# WL_144.net
KiCad netlist of a schematic drawn in Altium Designer
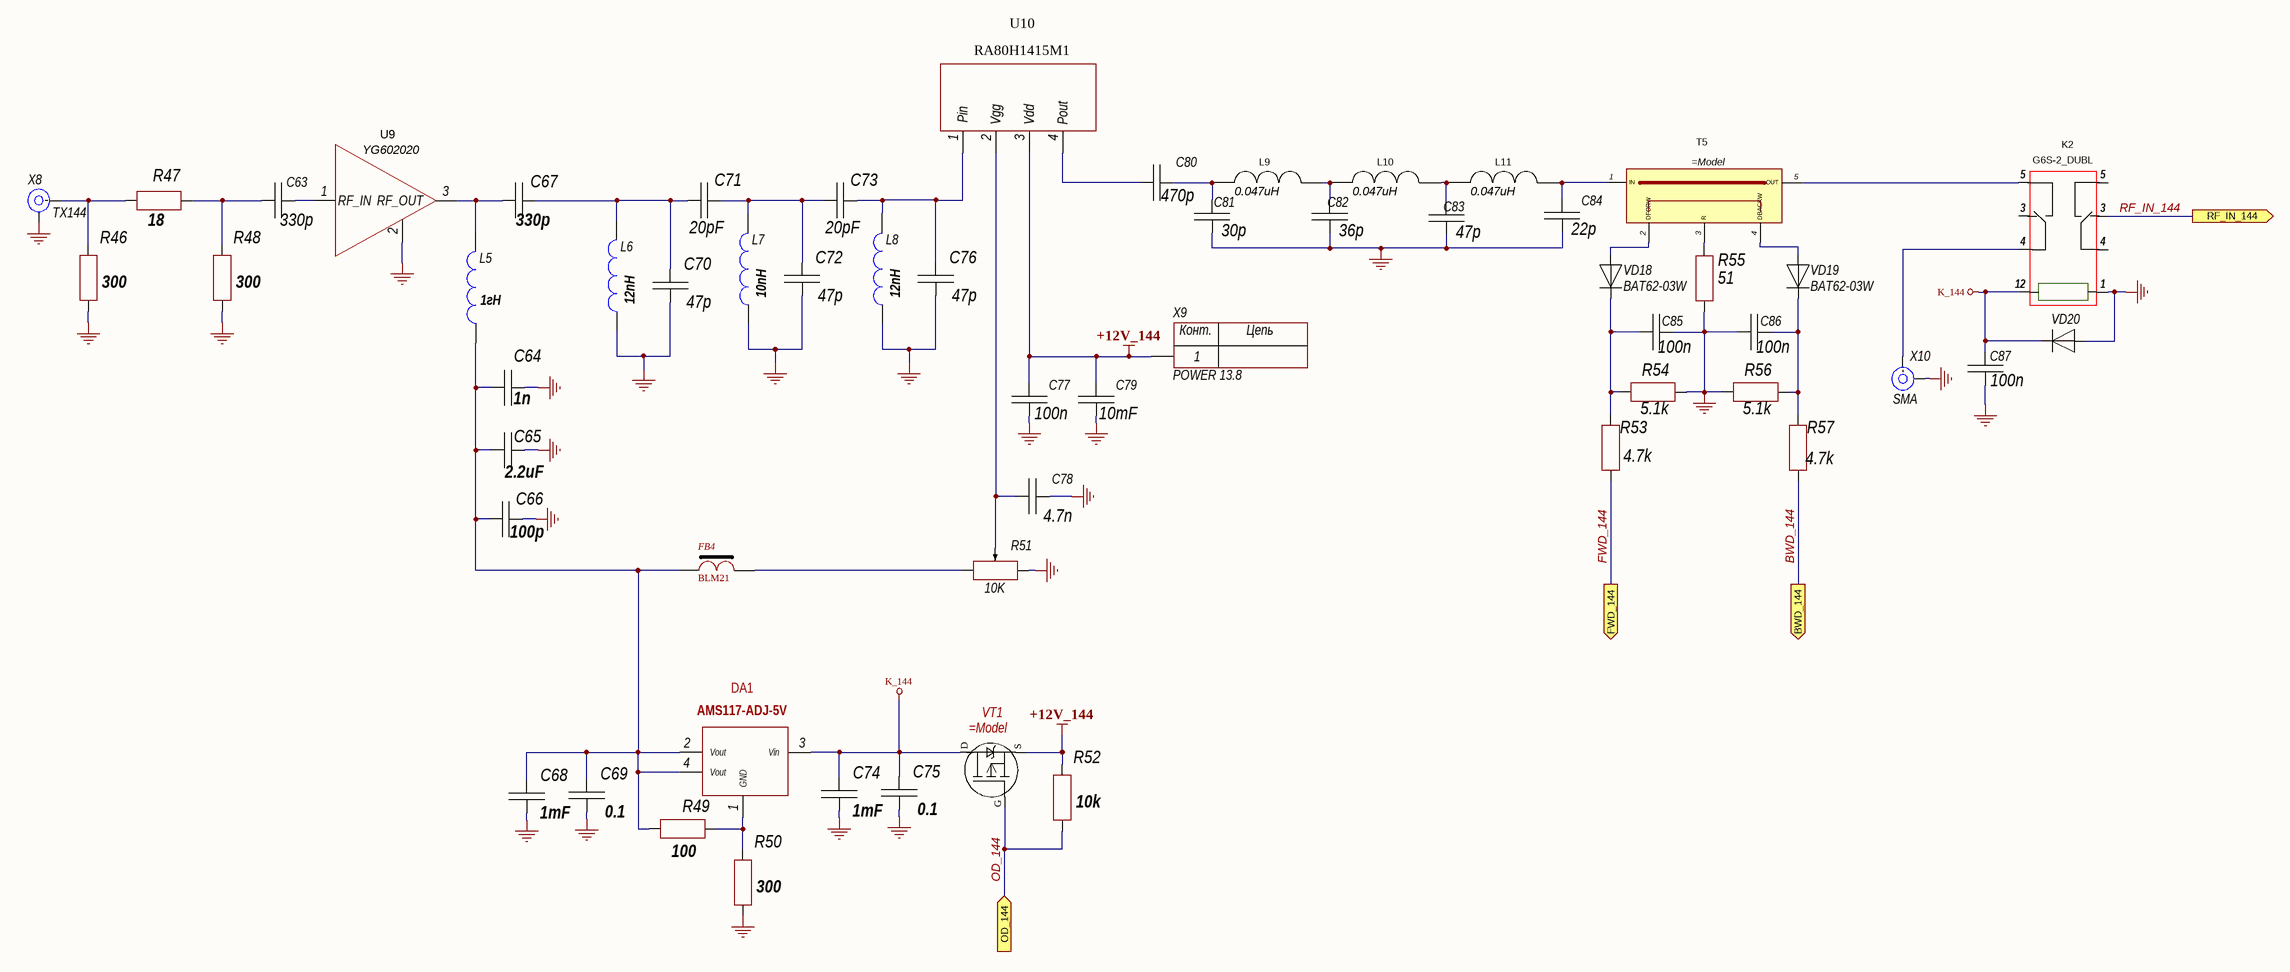
[diagram p0: WL_144.SchDoc]

(export (version "E")
  (design (tool "Eeschema 10.0.6"))
  (components
    (comp (ref "C63")
      (value "330p")
      (footprint "standard:CH0805C")
      (libsource (lib "Discrete") (part "Capacitor"))
    )
    (comp (ref "C64")
      (value "1n")
      (footprint "standard:CH0805C")
      (libsource (lib "Discrete") (part "Capacitor"))
    )
    (comp (ref "C65")
      (value "2.2uF")
      (footprint "standard:CH0805C")
      (libsource (lib "") (part "Capacitor_1"))
    )
    (comp (ref "C66")
      (value "100p")
      (footprint "standard:CH0805C")
      (libsource (lib "Discrete") (part "Capacitor"))
    )
    (comp (ref "C67")
      (value "330p")
      (footprint "standard:CH0805C")
      (libsource (lib "Discrete") (part "Capacitor"))
    )
    (comp (ref "C68")
      (value "1mF")
      (footprint "standard:CH0805C")
      (libsource (lib "Discrete") (part "Capacitor"))
    )
    (comp (ref "C69")
      (value "0.1")
      (footprint "standard:CH0805C")
      (libsource (lib "Discrete") (part "Capacitor"))
    )
    (comp (ref "C70")
      (value "47p")
      (footprint "standard:CH0805C")
      (libsource (lib "Discrete") (part "Capacitor"))
    )
    (comp (ref "C71")
      (value "20pF")
      (footprint "standard:CH0805C")
      (libsource (lib "Discrete") (part "Capacitor"))
    )
    (comp (ref "C72")
      (value "47p")
      (footprint "standard:CH0805C")
      (libsource (lib "Discrete") (part "Capacitor"))
    )
    (comp (ref "C73")
      (value "20pF")
      (footprint "standard:CH0805C")
      (libsource (lib "Discrete") (part "Capacitor"))
    )
    (comp (ref "C74")
      (value "1mF")
      (footprint "standard:CH0805C")
      (libsource (lib "Discrete") (part "Capacitor"))
    )
    (comp (ref "C75")
      (value "0.1")
      (footprint "standard:CH0805C")
      (libsource (lib "Discrete") (part "Capacitor"))
    )
    (comp (ref "C76")
      (value "47p")
      (footprint "standard:CH0805C")
      (libsource (lib "Discrete") (part "Capacitor"))
    )
    (comp (ref "C77")
      (value "100n")
      (footprint "standard:CH1206C")
      (libsource (lib "Discrete") (part "Capacitor"))
    )
    (comp (ref "C78")
      (value "4.7n")
      (footprint "standard:CH0805C")
      (libsource (lib "Discrete") (part "Capacitor"))
    )
    (comp (ref "C79")
      (value "10mF")
      (footprint "standard:CH1206C")
      (libsource (lib "Discrete") (part "Capacitor"))
    )
    (comp (ref "C80")
      (value "470p")
      (footprint "standard:CH1206C")
      (libsource (lib "Discrete") (part "Capacitor"))
    )
    (comp (ref "C81")
      (value "30p")
      (footprint "standard:CH1206C")
      (libsource (lib "Discrete") (part "Capacitor"))
    )
    (comp (ref "C82")
      (value "36p")
      (footprint "standard:CH1206C")
      (libsource (lib "Discrete") (part "Capacitor"))
    )
    (comp (ref "C83")
      (value "47p")
      (footprint "standard:CH1206C")
      (libsource (lib "Discrete") (part "Capacitor"))
    )
    (comp (ref "C84")
      (value "22p")
      (footprint "standard:CH1206C")
      (libsource (lib "Discrete") (part "Capacitor"))
    )
    (comp (ref "C85")
      (value "100n")
      (footprint "standard:CH0805C")
      (libsource (lib "Discrete") (part "Capacitor"))
    )
    (comp (ref "C86")
      (value "100n")
      (footprint "standard:CH0805C")
      (libsource (lib "Discrete") (part "Capacitor"))
    )
    (comp (ref "C87")
      (value "100n")
      (footprint "standard:CH0805C")
      (libsource (lib "Discrete") (part "Capacitor"))
    )
    (comp (ref "DA1") (value "AMS117-ADJ-5V") (footprint "SOT223") (libsource (lib "Analog") (part "AMS117")))
    (comp (ref "FB4") (value "BLM21") (footprint "CH0805L") (libsource (lib "Discrete") (part "FB-1")))
    (comp (ref "K2")
      (value "G6S-2_DUBL")
      (footprint "G6S-2_DUBL")
      (libsource (lib "Relay") (part "G6S-2_DUBL"))
    )
    (comp (ref "L5")
      (value "1гH")
      (footprint "katuhka")
      (libsource (lib "Transformers") (part "Inductor ring"))
    )
    (comp (ref "L6")
      (value "12nH")
      (footprint "katuhka")
      (libsource (lib "Transformers") (part "Inductor ring"))
    )
    (comp (ref "L7")
      (value "10nH")
      (footprint "katuhka")
      (libsource (lib "Transformers") (part "Inductor ring"))
    )
    (comp (ref "L8")
      (value "12nH")
      (footprint "katuhka")
      (libsource (lib "Transformers") (part "Inductor ring"))
    )
    (comp (ref "L9")
      (value "0.047uH")
      (footprint "L-FNC_V3")
      (libsource (lib "Transformers") (part "TRANS-1"))
    )
    (comp (ref "L10")
      (value "0.047uH")
      (footprint "L-FNC_V3")
      (libsource (lib "Transformers") (part "TRANS-1"))
    )
    (comp (ref "L11")
      (value "0.047uH")
      (footprint "L-FNC_V3")
      (libsource (lib "Transformers") (part "TRANS-1"))
    )
    (comp (ref "R46") (value "300") (footprint "standard:CH0805R") (libsource (lib "") (part "Resistor_1")))
    (comp (ref "R47")
      (value "18")
      (footprint "standard:CH0805R")
      (libsource (lib "Discrete") (part "Resistor"))
    )
    (comp (ref "R48") (value "300") (footprint "standard:CH0805R") (libsource (lib "") (part "Resistor_1")))
    (comp (ref "R49")
      (value "100")
      (footprint "standard:CH0805R")
      (libsource (lib "Discrete") (part "Resistor"))
    )
    (comp (ref "R50") (value "300") (footprint "standard:CH0805R") (libsource (lib "") (part "Resistor_1")))
    (comp (ref "R51")
      (value "10K")
      (footprint "custom:RES: 3296W")
      (libsource (lib "Discrete") (part "ADJ resistor"))
    )
    (comp (ref "R52") (value "10k") (footprint "standard:CH0805R") (libsource (lib "") (part "Resistor_1")))
    (comp (ref "R53") (value "4.7k") (footprint "standard:CH0805R") (libsource (lib "") (part "Resistor_2")))
    (comp (ref "R54")
      (value "5.1k")
      (footprint "standard:CH0805R")
      (libsource (lib "Discrete") (part "Resistor"))
    )
    (comp (ref "R55") (value "51") (footprint "standard:CH1206R") (libsource (lib "") (part "Resistor_1")))
    (comp (ref "R56")
      (value "5.1k")
      (footprint "standard:CH0805R")
      (libsource (lib "Discrete") (part "Resistor"))
    )
    (comp (ref "R57") (value "4.7k") (footprint "standard:CH0805R") (libsource (lib "") (part "Resistor_2")))
    (comp (ref "T5") (value "~") (footprint "SWR_D") (libsource (lib "Transformers") (part "VHF_KSV1")))
    (comp (ref "U9") (value "YG602020") (footprint "SOT89_123") (libsource (lib "Digital") (part "YG602020")))
    (comp (ref "U10")
      (value "RA80H1415M1")
      (footprint "RA80H1415M1 - duplicate")
      (libsource (lib "Digital") (part "RA80H1415M1"))
    )
    (comp (ref "VD18") (value "BAT62-03W") (footprint "1N4148") (libsource (lib "Diods") (part "Diod")))
    (comp (ref "VD19") (value "BAT62-03W") (footprint "1N4148") (libsource (lib "Diods") (part "Diod")))
    (comp (ref "VD20") (value "~") (footprint "1N4148") (libsource (lib "Diods") (part "Diod")))
    (comp (ref "VT1") (value "~") (footprint "SOT23_132") (libsource (lib "Transistor") (part "P-KANAL")))
    (comp (ref "X8")
      (value "TX144")
      (footprint "CON: u.Fl")
      (description "RF")
      (libsource (lib "Connectors") (part "SMA"))
    )
    (comp (ref "X9")
      (value "POWER 13.8")
      (footprint "CON: KNIFE_5MM")
      (libsource (lib "Connectors") (part "1-Connector"))
    )
    (comp (ref "X10")
      (value "SMA")
      (footprint "custom:CON: SMA")
      (description "RF")
      (libsource (lib "Connectors") (part "SMA"))
    )
  )
  (nets
    (net (code "1") (name "+12V_144") (class "Default")
      (node (ref "C77") (pin "2") (pinfunction "2_2") (pintype "power_in"))
      (node (ref "C79") (pin "2") (pinfunction "2_2") (pintype "power_in"))
      (node (ref "R52") (pin "2") (pinfunction "2_2") (pintype "passive"))
      (node (ref "U10") (pin "3") (pinfunction "Vdd_3") (pintype "passive"))
      (node (ref "VT1") (pin "2") (pinfunction "Исток_2") (pintype "passive"))
      (node (ref "X9") (pin "1") (pinfunction "1_1") (pintype "passive"))
    )
    (net (code "2") (name "/BWD_144") (class "Default")
      (node (ref "R57") (pin "2") (pinfunction "2_2") (pintype "passive"))
    )
    (net (code "3") (name "/FWD_144") (class "Default")
      (node (ref "R53") (pin "2") (pinfunction "2_2") (pintype "passive"))
    )
    (net (code "4") (name "/OD_144") (class "Default")
      (node (ref "R52") (pin "1") (pinfunction "1_1") (pintype "passive"))
      (node (ref "VT1") (pin "1") (pinfunction "Затвор(Gate)_1") (pintype "passive"))
    )
    (net (code "5") (name "/RF_IN_144") (class "Default")
      (node (ref "K2") (pin "3") (pinfunction "3_3") (pintype "passive"))
    )
    (net (code "6") (name "GND") (class "Default")
      (node (ref "C64") (pin "2") (pinfunction "2_2") (pintype "power_in"))
      (node (ref "C65") (pin "2") (pinfunction "2_2") (pintype "power_in"))
      (node (ref "C66") (pin "2") (pinfunction "2_2") (pintype "power_in"))
      (node (ref "C68") (pin "1") (pinfunction "1_1") (pintype "power_in"))
      (node (ref "C69") (pin "1") (pinfunction "1_1") (pintype "power_in"))
      (node (ref "C70") (pin "1") (pinfunction "1_1") (pintype "power_in"))
      (node (ref "C72") (pin "1") (pinfunction "1_1") (pintype "power_in"))
      (node (ref "C74") (pin "1") (pinfunction "1_1") (pintype "power_in"))
      (node (ref "C75") (pin "1") (pinfunction "1_1") (pintype "power_in"))
      (node (ref "C76") (pin "1") (pinfunction "1_1") (pintype "power_in"))
      (node (ref "C77") (pin "1") (pinfunction "1_1") (pintype "power_in"))
      (node (ref "C78") (pin "1") (pinfunction "1_1") (pintype "power_in"))
      (node (ref "C79") (pin "1") (pinfunction "1_1") (pintype "power_in"))
      (node (ref "C81") (pin "1") (pinfunction "1_1") (pintype "power_in"))
      (node (ref "C82") (pin "1") (pinfunction "1_1") (pintype "power_in"))
      (node (ref "C83") (pin "1") (pinfunction "1_1") (pintype "power_in"))
      (node (ref "C84") (pin "1") (pinfunction "1_1") (pintype "power_in"))
      (node (ref "C85") (pin "1") (pinfunction "1_1") (pintype "power_in"))
      (node (ref "C86") (pin "2") (pinfunction "2_2") (pintype "power_in"))
      (node (ref "C87") (pin "2") (pinfunction "2_2") (pintype "power_in"))
      (node (ref "K2") (pin "1") (pinfunction "1_1") (pintype "passive"))
      (node (ref "L6") (pin "2") (pinfunction "2_2") (pintype "passive"))
      (node (ref "L7") (pin "2") (pinfunction "2_2") (pintype "passive"))
      (node (ref "L8") (pin "2") (pinfunction "2_2") (pintype "passive"))
      (node (ref "R46") (pin "1") (pinfunction "1_1") (pintype "passive"))
      (node (ref "R48") (pin "1") (pinfunction "1_1") (pintype "passive"))
      (node (ref "R50") (pin "1") (pinfunction "1_1") (pintype "passive"))
      (node (ref "R51") (pin "1") (pinfunction "1_1") (pintype "passive"))
      (node (ref "R54") (pin "1") (pinfunction "1_1") (pintype "passive"))
      (node (ref "R55") (pin "1") (pinfunction "1_1") (pintype "passive"))
      (node (ref "R56") (pin "2") (pinfunction "2_2") (pintype "passive"))
      (node (ref "U9") (pin "2") (pinfunction "GND_2") (pintype "passive"))
      (node (ref "VD20") (pin "1") (pinfunction "1_1") (pintype "passive"))
      (node (ref "X10") (pin "2") (pinfunction "IN_2") (pintype "passive"))
      (node (ref "X8") (pin "2") (pinfunction "IN_2") (pintype "passive"))
    )
    (net (code "7") (name "K_144") (class "Default")
      (node (ref "C74") (pin "2") (pinfunction "2_2") (pintype "power_in"))
      (node (ref "C75") (pin "2") (pinfunction "2_2") (pintype "power_in"))
      (node (ref "C87") (pin "1") (pinfunction "1_1") (pintype "power_in"))
      (node (ref "DA1") (pin "3") (pinfunction "Vin_3") (pintype "passive"))
      (node (ref "K2") (pin "12") (pinfunction "12_12") (pintype "passive"))
      (node (ref "VD20") (pin "2") (pinfunction "2_2") (pintype "passive"))
      (node (ref "VT1") (pin "3") (pinfunction "Сток_3") (pintype "passive"))
    )
    (net (code "8") (name "Net-(C63-Pad2)") (class "Default")
      (node (ref "C63") (pin "2") (pinfunction "2_2") (pintype "power_in"))
      (node (ref "R47") (pin "1") (pinfunction "1_1") (pintype "passive"))
      (node (ref "R48") (pin "2") (pinfunction "2_2") (pintype "passive"))
    )
    (net (code "9") (name "Net-(C64-Pad1)") (class "Default")
      (node (ref "C64") (pin "1") (pinfunction "1_1") (pintype "power_in"))
      (node (ref "C65") (pin "1") (pinfunction "1_1") (pintype "power_in"))
      (node (ref "C66") (pin "1") (pinfunction "1_1") (pintype "power_in"))
      (node (ref "C68") (pin "2") (pinfunction "2_2") (pintype "power_in"))
      (node (ref "C69") (pin "2") (pinfunction "2_2") (pintype "power_in"))
      (node (ref "DA1") (pin "2") (pinfunction "Vout_2") (pintype "passive"))
      (node (ref "DA1") (pin "4") (pinfunction "Vout_4") (pintype "passive"))
      (node (ref "FB4") (pin "1") (pinfunction "1_1") (pintype "passive"))
      (node (ref "L5") (pin "2") (pinfunction "2_2") (pintype "passive"))
      (node (ref "R49") (pin "2") (pinfunction "2_2") (pintype "passive"))
    )
    (net (code "10") (name "Net-(C67-Pad2)") (class "Default")
      (node (ref "C67") (pin "2") (pinfunction "2_2") (pintype "power_in"))
      (node (ref "C70") (pin "2") (pinfunction "2_2") (pintype "power_in"))
      (node (ref "C71") (pin "1") (pinfunction "1_1") (pintype "power_in"))
      (node (ref "L6") (pin "1") (pinfunction "1_1") (pintype "passive"))
    )
    (net (code "11") (name "Net-(C71-Pad2)") (class "Default")
      (node (ref "C71") (pin "2") (pinfunction "2_2") (pintype "power_in"))
      (node (ref "C72") (pin "2") (pinfunction "2_2") (pintype "power_in"))
      (node (ref "C73") (pin "1") (pinfunction "1_1") (pintype "power_in"))
      (node (ref "L7") (pin "1") (pinfunction "1_1") (pintype "passive"))
    )
    (net (code "12") (name "Net-(C80-Pad1)") (class "Default")
      (node (ref "C80") (pin "1") (pinfunction "1_1") (pintype "power_in"))
      (node (ref "C81") (pin "2") (pinfunction "2_2") (pintype "power_in"))
      (node (ref "L9") (pin "1") (pinfunction "1_1") (pintype "power_in"))
    )
    (net (code "13") (name "Net-(C82-Pad2)") (class "Default")
      (node (ref "C82") (pin "2") (pinfunction "2_2") (pintype "power_in"))
      (node (ref "L10") (pin "1") (pinfunction "1_1") (pintype "power_in"))
      (node (ref "L9") (pin "2") (pinfunction "2_2") (pintype "power_in"))
    )
    (net (code "14") (name "Net-(C83-Pad2)") (class "Default")
      (node (ref "C83") (pin "2") (pinfunction "2_2") (pintype "power_in"))
      (node (ref "L10") (pin "2") (pinfunction "2_2") (pintype "power_in"))
      (node (ref "L11") (pin "1") (pinfunction "1_1") (pintype "power_in"))
    )
    (net (code "15") (name "Net-(C85-Pad2)") (class "Default")
      (node (ref "C85") (pin "2") (pinfunction "2_2") (pintype "power_in"))
      (node (ref "R53") (pin "1") (pinfunction "1_1") (pintype "passive"))
      (node (ref "R54") (pin "2") (pinfunction "2_2") (pintype "passive"))
      (node (ref "VD18") (pin "2") (pinfunction "2_2") (pintype "passive"))
    )
    (net (code "16") (name "Net-(C86-Pad1)") (class "Default")
      (node (ref "C86") (pin "1") (pinfunction "1_1") (pintype "power_in"))
      (node (ref "R56") (pin "1") (pinfunction "1_1") (pintype "passive"))
      (node (ref "R57") (pin "1") (pinfunction "1_1") (pintype "passive"))
      (node (ref "VD19") (pin "2") (pinfunction "2_2") (pintype "passive"))
    )
    (net (code "17") (name "Net-(DA1-GND)") (class "Default")
      (node (ref "DA1") (pin "1") (pinfunction "GND_1") (pintype "passive"))
      (node (ref "R49") (pin "1") (pinfunction "1_1") (pintype "passive"))
      (node (ref "R50") (pin "2") (pinfunction "2_2") (pintype "passive"))
    )
    (net (code "18") (name "Net-(FB4-Pad2)") (class "Default")
      (node (ref "FB4") (pin "2") (pinfunction "2_2") (pintype "passive"))
      (node (ref "R51") (pin "3") (pinfunction "3_3") (pintype "passive"))
    )
    (net (code "19") (name "Net-(K2-Pad4)_1") (class "Default")
      (node (ref "K2") (pin "4") (pinfunction "4_4") (pintype "passive"))
      (node (ref "X10") (pin "1") (pinfunction "IN_1") (pintype "passive"))
    )
    (net (code "20") (name "Net-(R46-Pad2)") (class "Default")
      (node (ref "R46") (pin "2") (pinfunction "2_2") (pintype "passive"))
      (node (ref "R47") (pin "2") (pinfunction "2_2") (pintype "passive"))
      (node (ref "X8") (pin "1") (pinfunction "IN_1") (pintype "passive"))
    )
    (net (code "21") (name "Net-(T5-DBACKW)") (class "Default")
      (node (ref "T5") (pin "4") (pinfunction "DBACKW_4") (pintype "passive"))
      (node (ref "VD19") (pin "1") (pinfunction "1_1") (pintype "passive"))
    )
    (net (code "22") (name "Net-(T5-DFORW)") (class "Default")
      (node (ref "T5") (pin "2") (pinfunction "DFORW_2") (pintype "passive"))
      (node (ref "VD18") (pin "1") (pinfunction "1_1") (pintype "passive"))
    )
    (net (code "23") (name "Net-(T5-IN)") (class "Default")
      (node (ref "C84") (pin "2") (pinfunction "2_2") (pintype "power_in"))
      (node (ref "L11") (pin "2") (pinfunction "2_2") (pintype "power_in"))
      (node (ref "T5") (pin "1") (pinfunction "IN_1") (pintype "passive"))
    )
    (net (code "24") (name "Net-(T5-OUT)") (class "Default")
      (node (ref "K2") (pin "5") (pinfunction "5_5") (pintype "passive"))
      (node (ref "T5") (pin "5") (pinfunction "OUT_5") (pintype "passive"))
    )
    (net (code "25") (name "Net-(T5-R)") (class "Default")
      (node (ref "R55") (pin "2") (pinfunction "2_2") (pintype "passive"))
      (node (ref "T5") (pin "3") (pinfunction "R_3") (pintype "passive"))
    )
    (net (code "26") (name "Net-(U9-RF_IN)") (class "Default")
      (node (ref "C63") (pin "1") (pinfunction "1_1") (pintype "power_in"))
      (node (ref "U9") (pin "1") (pinfunction "RF_IN_1") (pintype "passive"))
    )
    (net (code "27") (name "Net-(U9-RF_OUT)") (class "Default")
      (node (ref "C67") (pin "1") (pinfunction "1_1") (pintype "power_in"))
      (node (ref "L5") (pin "1") (pinfunction "1_1") (pintype "passive"))
      (node (ref "U9") (pin "3") (pinfunction "RF_OUT_3") (pintype "passive"))
    )
    (net (code "28") (name "Net-(U10-Pin)") (class "Default")
      (node (ref "C73") (pin "2") (pinfunction "2_2") (pintype "power_in"))
      (node (ref "C76") (pin "2") (pinfunction "2_2") (pintype "power_in"))
      (node (ref "L8") (pin "1") (pinfunction "1_1") (pintype "passive"))
      (node (ref "U10") (pin "1") (pinfunction "Pin_1") (pintype "passive"))
    )
    (net (code "29") (name "Net-(U10-Pout)") (class "Default")
      (node (ref "C80") (pin "2") (pinfunction "2_2") (pintype "power_in"))
      (node (ref "U10") (pin "4") (pinfunction "Pout_4") (pintype "passive"))
    )
    (net (code "30") (name "Net-(U10-Vgg)") (class "Default")
      (node (ref "C78") (pin "2") (pinfunction "2_2") (pintype "power_in"))
      (node (ref "R51") (pin "2") (pinfunction "2_2") (pintype "passive"))
      (node (ref "U10") (pin "2") (pinfunction "Vgg_2") (pintype "passive"))
    )
    (net (code "31") (name "unconnected-(K2-Pad3)") (class "Default")
      (node (ref "K2") (pin "3") (pinfunction "3_3") (pintype "passive"))
    )
    (net (code "32") (name "unconnected-(K2-Pad4)") (class "Default")
      (node (ref "K2") (pin "4") (pinfunction "4_4") (pintype "passive"))
    )
    (net (code "33") (name "unconnected-(K2-Pad5)") (class "Default")
      (node (ref "K2") (pin "5") (pinfunction "5_5") (pintype "passive"))
    )
  )
)
